# RS232Tranceiver.net
KiCad netlist of a schematic drawn in Altium Designer
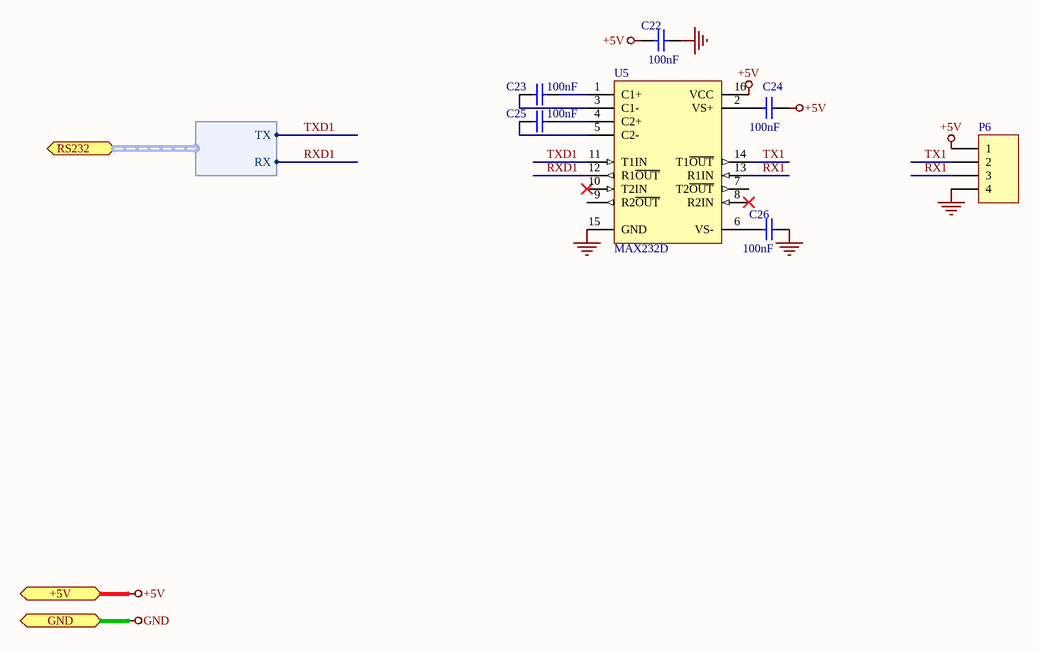
[diagram p0: RS232Tranceiver.SchDoc]

(export (version "E")
  (design (tool "Eeschema 10.0.6"))
  (components
    (comp (ref "C22")
      (value "100nF")
      (footprint "C-0805")
      (description "Capacitor")
      (fields (field (name "Comment") "104") (field (name "PUBLISHER") "Altium Limited"))
      (libsource (lib "Miscellaneous Devices") (part "Cap"))
    )
    (comp (ref "C23")
      (value "100nF")
      (footprint "C-0805")
      (description "Capacitor")
      (fields (field (name "Comment") "104") (field (name "PUBLISHER") "Altium Limited"))
      (libsource (lib "Miscellaneous Devices") (part "Cap"))
    )
    (comp (ref "C24")
      (value "100nF")
      (footprint "C-0805")
      (description "Capacitor")
      (fields (field (name "Comment") "104") (field (name "PUBLISHER") "Altium Limited"))
      (libsource (lib "Miscellaneous Devices") (part "Cap"))
    )
    (comp (ref "C25")
      (value "100nF")
      (footprint "C-0805")
      (description "Capacitor")
      (fields (field (name "Comment") "104") (field (name "PUBLISHER") "Altium Limited"))
      (libsource (lib "Miscellaneous Devices") (part "Cap"))
    )
    (comp (ref "C26")
      (value "100nF")
      (footprint "C-0805")
      (description "Capacitor")
      (fields (field (name "Comment") "104") (field (name "PUBLISHER") "Altium Limited"))
      (libsource (lib "Miscellaneous Devices") (part "Cap"))
    )
    (comp (ref "P6")
      (value "XH2.54-4P")
      (footprint "CONN-XH2.54-4P")
      (description "Header, 4-Pin")
      (libsource (lib "Miscellaneous Connectors") (part "Header 4"))
    )
    (comp (ref "U5")
      (value "MAX232D")
      (footprint "SOIC-16")
      (description "Dual EIA-232 Driver/Receiver")
      (fields (field (name "PUBLISHER") "Altium Limited"))
      (libsource (lib "TI Interface Line Transceiver") (part "MAX232D"))
    )
  )
  (nets
    (net (code "2") (name "+5V") (class "Default")
      (node (ref "C22") (pin "1") (pinfunction "1_1") (pintype "passive"))
      (node (ref "C24") (pin "1") (pinfunction "1_1") (pintype "passive"))
      (node (ref "P6") (pin "1") (pinfunction "1_1") (pintype "passive"))
      (node (ref "U5") (pin "16") (pinfunction "VCC_16") (pintype "power_in"))
    )
    (net (code "3") (name "/RX1") (class "Default")
      (node (ref "P6") (pin "3") (pinfunction "3_3") (pintype "passive"))
      (node (ref "U5") (pin "13") (pinfunction "R1IN_13") (pintype "input"))
    )
    (net (code "4") (name "/RXD1") (class "Default")
      (node (ref "U5") (pin "12") (pinfunction "R1~{OUT}_12") (pintype "output"))
    )
    (net (code "5") (name "/TX1") (class "Default")
      (node (ref "P6") (pin "2") (pinfunction "2_2") (pintype "passive"))
      (node (ref "U5") (pin "14") (pinfunction "T1~{OUT}_14") (pintype "output"))
    )
    (net (code "6") (name "/TXD1") (class "Default")
      (node (ref "U5") (pin "11") (pinfunction "T1IN_11") (pintype "input"))
    )
    (net (code "8") (name "GND") (class "Default")
      (node (ref "C22") (pin "2") (pinfunction "2_2") (pintype "passive"))
      (node (ref "C26") (pin "2") (pinfunction "2_2") (pintype "passive"))
      (node (ref "P6") (pin "4") (pinfunction "4_4") (pintype "passive"))
      (node (ref "U5") (pin "15") (pinfunction "GND_15") (pintype "power_in"))
    )
    (net (code "9") (name "Net-(U5-C1+)") (class "Default")
      (node (ref "C23") (pin "2") (pinfunction "2_2") (pintype "passive"))
      (node (ref "U5") (pin "1") (pinfunction "C1+_1") (pintype "passive"))
    )
    (net (code "10") (name "Net-(U5-C1-)") (class "Default")
      (node (ref "C23") (pin "1") (pinfunction "1_1") (pintype "passive"))
      (node (ref "U5") (pin "3") (pinfunction "C1-_3") (pintype "passive"))
    )
    (net (code "11") (name "Net-(U5-C2+)") (class "Default")
      (node (ref "C25") (pin "2") (pinfunction "2_2") (pintype "passive"))
      (node (ref "U5") (pin "4") (pinfunction "C2+_4") (pintype "passive"))
    )
    (net (code "12") (name "Net-(U5-C2-)") (class "Default")
      (node (ref "C25") (pin "1") (pinfunction "1_1") (pintype "passive"))
      (node (ref "U5") (pin "5") (pinfunction "C2-_5") (pintype "passive"))
    )
    (net (code "13") (name "Net-(U5-VS+)") (class "Default")
      (node (ref "C24") (pin "2") (pinfunction "2_2") (pintype "passive"))
      (node (ref "U5") (pin "2") (pinfunction "VS+_2") (pintype "power_in"))
    )
    (net (code "14") (name "Net-(U5-VS-)") (class "Default")
      (node (ref "C26") (pin "1") (pinfunction "1_1") (pintype "passive"))
      (node (ref "U5") (pin "6") (pinfunction "VS-_6") (pintype "power_in"))
    )
    (net (code "15") (name "unconnected-(U5-R2IN-Pad8)") (class "Default")
      (node (ref "U5") (pin "8") (pinfunction "R2IN_8") (pintype "input+no_connect"))
    )
    (net (code "16") (name "unconnected-(U5-R2~{OUT}-Pad9)") (class "Default")
      (node (ref "U5") (pin "9") (pinfunction "R2~{OUT}_9") (pintype "output"))
    )
    (net (code "17") (name "unconnected-(U5-T2IN-Pad10)") (class "Default")
      (node (ref "U5") (pin "10") (pinfunction "T2IN_10") (pintype "input+no_connect"))
    )
    (net (code "18") (name "unconnected-(U5-T2~{OUT}-Pad7)") (class "Default")
      (node (ref "U5") (pin "7") (pinfunction "T2~{OUT}_7") (pintype "output"))
    )
  )
)
